# LEDs.net
KiCad netlist of a schematic drawn in Altium Designer
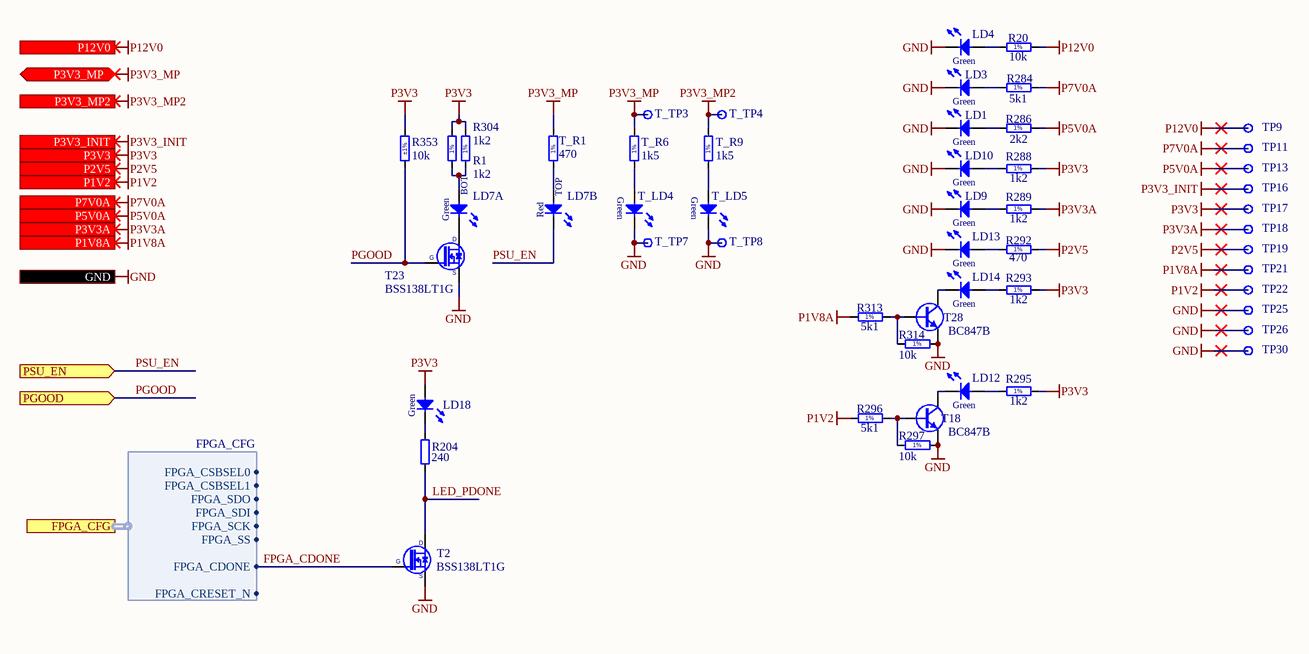
[diagram p0: LEDs.SchDoc]

(export (version "E")
  (design (tool "Eeschema 10.0.6"))
  (components
    (comp (ref "LD1")
      (value "Green")
      (footprint "LED_KINGBRIGHT_KPH-1608CGCK")
      (description "LED Green 1C 2A")
      (fields
        (field (name "PART NUMBER") "LED_KINGBRIGHT_KPH-1608CGCK")
        (field (name "MANUFACTURER") "KINGBRIGHT")
        (field (name "AUTHOR") "CERN DEM JLC")
      )
      (libsource (lib "ICs And Semiconductors") (part "LED Green 1C 2A"))
    )
    (comp (ref "LD3")
      (value "Green")
      (footprint "LED_KINGBRIGHT_KPH-1608CGCK")
      (description "LED Green 1C 2A")
      (fields
        (field (name "PART NUMBER") "LED_KINGBRIGHT_KPH-1608CGCK")
        (field (name "MANUFACTURER") "KINGBRIGHT")
        (field (name "AUTHOR") "CERN DEM JLC")
      )
      (libsource (lib "ICs And Semiconductors") (part "LED Green 1C 2A"))
    )
    (comp (ref "LD4")
      (value "Green")
      (footprint "LED_KINGBRIGHT_KPH-1608CGCK")
      (description "LED Green 1C 2A")
      (fields
        (field (name "PART NUMBER") "LED_KINGBRIGHT_KPH-1608CGCK")
        (field (name "MANUFACTURER") "KINGBRIGHT")
        (field (name "AUTHOR") "CERN DEM JLC")
      )
      (libsource (lib "ICs And Semiconductors") (part "LED Green 1C 2A"))
    )
    (comp (ref "LD7")
      (value "Red/Green")
      (footprint "LED_DIALIGHT_571-0112F")
      (description "2x LED  Botom Green, Top Red")
      (fields
        (field (name "PART NUMBER") "LED_DIALIGHT_571-0112F")
        (field (name "MANUFACTURER") "DIALIGHT")
        (field (name "AUTHOR") "CERN DEM JLC")
      )
      (libsource (lib "ICs And Semiconductors") (part "LED x2 G-1C2A-BOT_R-3C4A-TOP"))
    )
    (comp (ref "LD9")
      (value "Green")
      (footprint "LED_KINGBRIGHT_KPH-1608CGCK")
      (description "LED Green 1C 2A")
      (fields
        (field (name "PART NUMBER") "LED_KINGBRIGHT_KPH-1608CGCK")
        (field (name "MANUFACTURER") "KINGBRIGHT")
        (field (name "AUTHOR") "CERN DEM JLC")
      )
      (libsource (lib "ICs And Semiconductors") (part "LED Green 1C 2A"))
    )
    (comp (ref "LD10")
      (value "Green")
      (footprint "LED_KINGBRIGHT_KPH-1608CGCK")
      (description "LED Green 1C 2A")
      (fields
        (field (name "PART NUMBER") "LED_KINGBRIGHT_KPH-1608CGCK")
        (field (name "MANUFACTURER") "KINGBRIGHT")
        (field (name "AUTHOR") "CERN DEM JLC")
      )
      (libsource (lib "ICs And Semiconductors") (part "LED Green 1C 2A"))
    )
    (comp (ref "LD12")
      (value "Green")
      (footprint "LED_KINGBRIGHT_KPH-1608CGCK")
      (description "LED Green 1C 2A")
      (fields
        (field (name "PART NUMBER") "LED_KINGBRIGHT_KPH-1608CGCK")
        (field (name "MANUFACTURER") "KINGBRIGHT")
        (field (name "AUTHOR") "CERN DEM JLC")
      )
      (libsource (lib "ICs And Semiconductors") (part "LED Green 1C 2A"))
    )
    (comp (ref "LD13")
      (value "Green")
      (footprint "LED_KINGBRIGHT_KPH-1608CGCK")
      (description "LED Green 1C 2A")
      (fields
        (field (name "PART NUMBER") "LED_KINGBRIGHT_KPH-1608CGCK")
        (field (name "MANUFACTURER") "KINGBRIGHT")
        (field (name "AUTHOR") "CERN DEM JLC")
      )
      (libsource (lib "ICs And Semiconductors") (part "LED Green 1C 2A"))
    )
    (comp (ref "LD14")
      (value "Green")
      (footprint "LED_KINGBRIGHT_KPH-1608CGCK")
      (description "LED Green 1C 2A")
      (fields
        (field (name "PART NUMBER") "LED_KINGBRIGHT_KPH-1608CGCK")
        (field (name "MANUFACTURER") "KINGBRIGHT")
        (field (name "AUTHOR") "CERN DEM JLC")
      )
      (libsource (lib "ICs And Semiconductors") (part "LED Green 1C 2A"))
    )
    (comp (ref "LD18")
      (value "Green")
      (footprint "LED_AVAGO_HSME-C120")
      (description "LED Green 1C 2A")
      (fields
        (field (name "PART NUMBER") "LED_AVAGO_HSME-C120")
        (field (name "MANUFACTURER") "AVAGO TECHNOLOGIES")
        (field (name "AUTHOR") "CERN DEM JMW")
      )
      (libsource (lib "ICs And Semiconductors") (part "LED Green 1C 2A"))
    )
    (comp (ref "R1")
      (value "1k2")
      (footprint "RESC1608X55N")
      (description "Resistor - 1%")
      (fields
        (field (name "PART NUMBER") "R0603_1K2_1%_0.1W_100PPM")
        (field (name "POWER") "0.1W")
        (field (name "AUTHOR") "CERN DEM JLC")
      )
      (libsource (lib "Resistors") (part "Resistor - 1%"))
    )
    (comp (ref "R20")
      (value "10k")
      (footprint "RESC1005X40N")
      (description "Resistor - 1%")
      (fields
        (field (name "PART NUMBER") "R0402_10K_1%_0.0625W_100PPM")
        (field (name "POWER") "0.0625W")
        (field (name "AUTHOR") "CERN DEM JLC")
      )
      (libsource (lib "Resistors") (part "Resistor - 1%"))
    )
    (comp (ref "R204")
      (value "240")
      (footprint "RESC1005X40N")
      (description "Resistor - 1%")
      (fields
        (field (name "PART NUMBER") "R0402_240R_1%_0.0625W_100PPM")
        (field (name "POWER") "0.0625W")
        (field (name "AUTHOR") "CERN DEM JLC")
      )
      (libsource (lib "Resistors") (part "Resistor - 1%"))
    )
    (comp (ref "R284")
      (value "5k1")
      (footprint "RESC1005X40N")
      (description "Resistor - 1%")
      (fields
        (field (name "PART NUMBER") "R0402_5K1_1%_0.0625W_100PPM")
        (field (name "POWER") "0.0625W")
        (field (name "AUTHOR") "CERN DEM JLC")
      )
      (libsource (lib "Resistors") (part "Resistor - 1%"))
    )
    (comp (ref "R286")
      (value "2k2")
      (footprint "RESC1005X40N")
      (description "Resistor - 1%")
      (fields
        (field (name "PART NUMBER") "R0402_2K2_1%_0.0625W_100PPM")
        (field (name "POWER") "0.0625W")
        (field (name "AUTHOR") "CERN DEM JLC")
      )
      (libsource (lib "Resistors") (part "Resistor - 1%"))
    )
    (comp (ref "R288")
      (value "1k2")
      (footprint "RESC1608X55N")
      (description "Resistor - 1%")
      (fields
        (field (name "PART NUMBER") "R0603_1K2_1%_0.1W_100PPM")
        (field (name "POWER") "0.1W")
        (field (name "AUTHOR") "CERN DEM JLC")
      )
      (libsource (lib "Resistors") (part "Resistor - 1%"))
    )
    (comp (ref "R289")
      (value "1k2")
      (footprint "RESC1608X55N")
      (description "Resistor - 1%")
      (fields
        (field (name "PART NUMBER") "R0603_1K2_1%_0.1W_100PPM")
        (field (name "POWER") "0.1W")
        (field (name "AUTHOR") "CERN DEM JLC")
      )
      (libsource (lib "Resistors") (part "Resistor - 1%"))
    )
    (comp (ref "R292")
      (value "470")
      (footprint "RESC1005X40N")
      (description "Resistor - 1%")
      (fields
        (field (name "PART NUMBER") "R0402_470R_1%_0.0625W_100PPM")
        (field (name "POWER") "0.0625W")
        (field (name "AUTHOR") "CERN DEM JLC")
      )
      (libsource (lib "Resistors") (part "Resistor - 1%"))
    )
    (comp (ref "R293")
      (value "1k2")
      (footprint "RESC1608X55N")
      (description "Resistor - 1%")
      (fields
        (field (name "PART NUMBER") "R0603_1K2_1%_0.1W_100PPM")
        (field (name "POWER") "0.1W")
        (field (name "AUTHOR") "CERN DEM JLC")
      )
      (libsource (lib "Resistors") (part "Resistor - 1%"))
    )
    (comp (ref "R295")
      (value "1k2")
      (footprint "RESC1608X55N")
      (description "Resistor - 1%")
      (fields
        (field (name "PART NUMBER") "R0603_1K2_1%_0.1W_100PPM")
        (field (name "POWER") "0.1W")
        (field (name "AUTHOR") "CERN DEM JLC")
      )
      (libsource (lib "Resistors") (part "Resistor - 1%"))
    )
    (comp (ref "R296")
      (value "5k1")
      (footprint "RESC1005X40N")
      (description "Resistor - 1%")
      (fields
        (field (name "PART NUMBER") "R0402_5K1_1%_0.0625W_100PPM")
        (field (name "POWER") "0.0625W")
        (field (name "AUTHOR") "CERN DEM JLC")
      )
      (libsource (lib "Resistors") (part "Resistor - 1%"))
    )
    (comp (ref "R297")
      (value "10k")
      (footprint "RESC1005X40N")
      (description "Resistor - 1%")
      (fields
        (field (name "PART NUMBER") "R0402_10K_1%_0.0625W_100PPM")
        (field (name "POWER") "0.0625W")
        (field (name "AUTHOR") "CERN DEM JLC")
      )
      (libsource (lib "Resistors") (part "Resistor - 1%"))
    )
    (comp (ref "R304")
      (value "1k2")
      (footprint "RESC1608X55N")
      (description "Resistor - 1%")
      (fields
        (field (name "PART NUMBER") "R0603_1K2_1%_0.1W_100PPM")
        (field (name "POWER") "0.1W")
        (field (name "AUTHOR") "CERN DEM JLC")
      )
      (libsource (lib "Resistors") (part "Resistor - 1%"))
    )
    (comp (ref "R313")
      (value "5k1")
      (footprint "RESC1005X40N")
      (description "Resistor - 1%")
      (fields
        (field (name "PART NUMBER") "R0402_5K1_1%_0.0625W_100PPM")
        (field (name "POWER") "0.0625W")
        (field (name "AUTHOR") "CERN DEM JLC")
      )
      (libsource (lib "Resistors") (part "Resistor - 1%"))
    )
    (comp (ref "R314")
      (value "10k")
      (footprint "RESC1005X40N")
      (description "Resistor - 1%")
      (fields
        (field (name "PART NUMBER") "R0402_10K_1%_0.0625W_100PPM")
        (field (name "POWER") "0.0625W")
        (field (name "AUTHOR") "CERN DEM JLC")
      )
      (libsource (lib "Resistors") (part "Resistor - 1%"))
    )
    (comp (ref "R353")
      (value "10k")
      (footprint "RESC1005X40N")
      (description "Resistor - 1%")
      (fields
        (field (name "TOLERANCE") "±1%")
        (field (name "PART NUMBER") "R0402_10K_1%_0.0625W_100PPM")
        (field (name "POWER") "0.0625W")
        (field (name "AUTHOR") "CERN DEM JLC")
      )
      (libsource (lib "Resistors") (part "Resistor - 1%"))
    )
    (comp (ref "T2")
      (value "BSS138LT1G")
      (footprint "SOT95P240X110-3N")
      (description "N-CHANNEL MOSFET WITH DIODE")
      (fields (field (name "MANUFACTURER") "ON SEMICONDUCTOR") (field (name "AUTHOR") "CERN DEM JLC"))
      (libsource (lib "ICs And Semiconductors") (part "N-MOSFET-D 1G 2S 3D"))
    )
    (comp (ref "T18")
      (value "BC847B")
      (footprint "SOT95P230X110-3N")
      (description "NPN Transistor")
      (fields (field (name "MANUFACTURER") "NXP SEMICONDUCTORS") (field (name "AUTHOR") "CERN DEM JLC"))
      (libsource (lib "ICs And Semiconductors") (part "NPN B1 E2 C3"))
    )
    (comp (ref "T23")
      (value "BSS138LT1G")
      (footprint "SOT95P240X110-3N")
      (description "N-CHANNEL MOSFET WITH DIODE")
      (fields
        (field (name "MANUFACTURER") "ON SEMICONDUCTOR")
        (field (name "MANUFACTURER PART NUMBER") "BSS138L")
        (field (name "AUTHOR") "CERN DEM JLC")
      )
      (libsource (lib "ICs And Semiconductors") (part "N-MOSFET-D 1G 2S 3D"))
    )
    (comp (ref "T28")
      (value "BC847B")
      (footprint "SOT95P230X110-3N")
      (description "NPN Transistor")
      (fields (field (name "MANUFACTURER") "NXP SEMICONDUCTORS") (field (name "AUTHOR") "CERN DEM JLC"))
      (libsource (lib "ICs And Semiconductors") (part "NPN B1 E2 C3"))
    )
    (comp (ref "TP9")
      (value "Test Point")
      (footprint "TPS127")
      (fields (field (name "PART NUMBER") "SMD_PAD_1.27X1.27MM") (field (name "AUTHOR") "CERN DEM JLC"))
      (libsource (lib "Eletro-mechanical") (part "Test Point"))
    )
    (comp (ref "TP11")
      (value "Test Point")
      (footprint "TPS127")
      (fields (field (name "PART NUMBER") "SMD_PAD_1.27X1.27MM") (field (name "AUTHOR") "CERN DEM JLC"))
      (libsource (lib "Eletro-mechanical") (part "Test Point"))
    )
    (comp (ref "TP13")
      (value "Test Point")
      (footprint "TPS127")
      (fields (field (name "PART NUMBER") "SMD_PAD_1.27X1.27MM") (field (name "AUTHOR") "CERN DEM JLC"))
      (libsource (lib "Eletro-mechanical") (part "Test Point"))
    )
    (comp (ref "TP16")
      (value "Test Point")
      (footprint "TPS127")
      (fields (field (name "PART NUMBER") "SMD_PAD_1.27X1.27MM") (field (name "AUTHOR") "CERN DEM JLC"))
      (libsource (lib "Eletro-mechanical") (part "Test Point"))
    )
    (comp (ref "TP17")
      (value "Test Point")
      (footprint "TPS127")
      (fields (field (name "PART NUMBER") "SMD_PAD_1.27X1.27MM") (field (name "AUTHOR") "CERN DEM JLC"))
      (libsource (lib "Eletro-mechanical") (part "Test Point"))
    )
    (comp (ref "TP18")
      (value "Test Point")
      (footprint "TPS127")
      (fields (field (name "PART NUMBER") "SMD_PAD_1.27X1.27MM") (field (name "AUTHOR") "CERN DEM JLC"))
      (libsource (lib "Eletro-mechanical") (part "Test Point"))
    )
    (comp (ref "TP19")
      (value "Test Point")
      (footprint "TPS127")
      (fields (field (name "PART NUMBER") "SMD_PAD_1.27X1.27MM") (field (name "AUTHOR") "CERN DEM JLC"))
      (libsource (lib "Eletro-mechanical") (part "Test Point"))
    )
    (comp (ref "TP21")
      (value "Test Point")
      (footprint "TPS127")
      (fields (field (name "PART NUMBER") "SMD_PAD_1.27X1.27MM") (field (name "AUTHOR") "CERN DEM JLC"))
      (libsource (lib "Eletro-mechanical") (part "Test Point"))
    )
    (comp (ref "TP22")
      (value "Test Point")
      (footprint "TPS127")
      (fields (field (name "PART NUMBER") "SMD_PAD_1.27X1.27MM") (field (name "AUTHOR") "CERN DEM JLC"))
      (libsource (lib "Eletro-mechanical") (part "Test Point"))
    )
    (comp (ref "TP25")
      (value "Test Point")
      (footprint "TPS127")
      (fields (field (name "PART NUMBER") "SMD_PAD_1.27X1.27MM") (field (name "AUTHOR") "CERN DEM JLC"))
      (libsource (lib "Eletro-mechanical") (part "Test Point"))
    )
    (comp (ref "TP26")
      (value "Test Point")
      (footprint "TPS127")
      (fields (field (name "PART NUMBER") "SMD_PAD_1.27X1.27MM") (field (name "AUTHOR") "CERN DEM JLC"))
      (libsource (lib "Eletro-mechanical") (part "Test Point"))
    )
    (comp (ref "TP30")
      (value "Test Point")
      (footprint "TPS127")
      (fields (field (name "PART NUMBER") "SMD_PAD_1.27X1.27MM") (field (name "AUTHOR") "CERN DEM JLC"))
      (libsource (lib "Eletro-mechanical") (part "Test Point"))
    )
    (comp (ref "T_LD4")
      (value "Green")
      (footprint "LED_KINGBRIGHT_KPH-1608CGCK")
      (description "LED Green 1C 2A")
      (fields
        (field (name "PART NUMBER") "LED_KINGBRIGHT_KPH-1608CGCK")
        (field (name "MANUFACTURER") "KINGBRIGHT")
        (field (name "AUTHOR") "CERN DEM JLC")
      )
      (libsource (lib "") (part "LED Green 1C 2A_1"))
    )
    (comp (ref "T_LD5")
      (value "Green")
      (footprint "LED_KINGBRIGHT_KPH-1608CGCK")
      (description "LED Green 1C 2A")
      (fields
        (field (name "PART NUMBER") "LED_KINGBRIGHT_KPH-1608CGCK")
        (field (name "MANUFACTURER") "KINGBRIGHT")
        (field (name "AUTHOR") "CERN DEM JLC")
      )
      (libsource (lib "") (part "LED Green 1C 2A_1"))
    )
    (comp (ref "T_R1")
      (value "470")
      (footprint "RESC1005X40N")
      (description "Resistor - 1%")
      (fields
        (field (name "PART NUMBER") "R0402_470R_1%_0.0625W_100PPM")
        (field (name "POWER") "0.0625W")
        (field (name "AUTHOR") "CERN DEM JLC")
      )
      (libsource (lib "Resistors") (part "Resistor - 1%"))
    )
    (comp (ref "T_R6")
      (value "1k5")
      (footprint "RESC1608X55N")
      (description "Resistor - 1%")
      (fields
        (field (name "PART NUMBER") "R0603_1K5_1%_0.1W_100PPM")
        (field (name "POWER") "0.1W")
        (field (name "AUTHOR") "CERN DEM JLC")
      )
      (libsource (lib "Resistors") (part "Resistor - 1%"))
    )
    (comp (ref "T_R9")
      (value "1k5")
      (footprint "RESC1608X55N")
      (description "Resistor - 1%")
      (fields
        (field (name "PART NUMBER") "R0603_1K5_1%_0.1W_100PPM")
        (field (name "POWER") "0.1W")
        (field (name "AUTHOR") "CERN DEM JLC")
      )
      (libsource (lib "Resistors") (part "Resistor - 1%"))
    )
    (comp (ref "T_TP3")
      (value "Test Point")
      (footprint "TPS127")
      (fields (field (name "PART NUMBER") "SMD_PAD_1.27X1.27MM") (field (name "AUTHOR") "CERN DEM JLC"))
      (libsource (lib "Eletro-mechanical") (part "Test Point"))
    )
    (comp (ref "T_TP4")
      (value "Test Point")
      (footprint "TPS127")
      (fields (field (name "PART NUMBER") "SMD_PAD_1.27X1.27MM") (field (name "AUTHOR") "CERN DEM JLC"))
      (libsource (lib "Eletro-mechanical") (part "Test Point"))
    )
    (comp (ref "T_TP7")
      (value "Test Point")
      (footprint "TPS127")
      (fields (field (name "PART NUMBER") "SMD_PAD_1.27X1.27MM") (field (name "AUTHOR") "CERN DEM JLC"))
      (libsource (lib "Eletro-mechanical") (part "Test Point"))
    )
    (comp (ref "T_TP8")
      (value "Test Point")
      (footprint "TPS127")
      (fields (field (name "PART NUMBER") "SMD_PAD_1.27X1.27MM") (field (name "AUTHOR") "CERN DEM JLC"))
      (libsource (lib "Eletro-mechanical") (part "Test Point"))
    )
  )
  (nets
    (net (code "2") (name "/FPGA_CDONE") (class "Default")
      (node (ref "T2") (pin "1") (pinfunction "G_1") (pintype "passive"))
    )
    (net (code "3") (name "/LED_PDONE") (class "Default")
      (node (ref "R204") (pin "1") (pinfunction "1_1") (pintype "passive"))
      (node (ref "T2") (pin "3") (pinfunction "D_3") (pintype "passive"))
    )
    (net (code "4") (name "/PGOOD") (class "Default")
      (node (ref "R353") (pin "1") (pinfunction "1_1") (pintype "passive"))
      (node (ref "T23") (pin "1") (pinfunction "G_1") (pintype "passive"))
    )
    (net (code "5") (name "/PSU_EN") (class "Default")
      (node (ref "LD7") (pin "3") (pinfunction "C_3") (pintype "passive"))
    )
    (net (code "7") (name "GND") (class "Default")
      (node (ref "LD1") (pin "1") (pinfunction "C_1") (pintype "passive"))
      (node (ref "LD10") (pin "1") (pinfunction "C_1") (pintype "passive"))
      (node (ref "LD13") (pin "1") (pinfunction "C_1") (pintype "passive"))
      (node (ref "LD3") (pin "1") (pinfunction "C_1") (pintype "passive"))
      (node (ref "LD4") (pin "1") (pinfunction "C_1") (pintype "passive"))
      (node (ref "LD9") (pin "1") (pinfunction "C_1") (pintype "passive"))
      (node (ref "R297") (pin "2") (pinfunction "2_2") (pintype "passive"))
      (node (ref "R314") (pin "2") (pinfunction "2_2") (pintype "passive"))
      (node (ref "T18") (pin "2") (pinfunction "E_2") (pintype "passive"))
      (node (ref "T2") (pin "2") (pinfunction "S_2") (pintype "passive"))
      (node (ref "T23") (pin "2") (pinfunction "S_2") (pintype "passive"))
      (node (ref "T28") (pin "2") (pinfunction "E_2") (pintype "passive"))
      (node (ref "TP25") (pin "1") (pinfunction "1_1") (pintype "bidirectional"))
      (node (ref "TP26") (pin "1") (pinfunction "1_1") (pintype "bidirectional"))
      (node (ref "TP30") (pin "1") (pinfunction "1_1") (pintype "bidirectional"))
      (node (ref "T_LD4") (pin "1") (pinfunction "C_1") (pintype "passive"))
      (node (ref "T_LD5") (pin "1") (pinfunction "C_1") (pintype "passive"))
      (node (ref "T_TP7") (pin "1") (pinfunction "1_1") (pintype "bidirectional"))
      (node (ref "T_TP8") (pin "1") (pinfunction "1_1") (pintype "bidirectional"))
    )
    (net (code "8") (name "Net-(LD1-A)") (class "Default")
      (node (ref "LD1") (pin "2") (pinfunction "A_2") (pintype "passive"))
      (node (ref "R286") (pin "1") (pinfunction "1_1") (pintype "passive"))
    )
    (net (code "9") (name "Net-(LD3-A)") (class "Default")
      (node (ref "LD3") (pin "2") (pinfunction "A_2") (pintype "passive"))
      (node (ref "R284") (pin "1") (pinfunction "1_1") (pintype "passive"))
    )
    (net (code "10") (name "Net-(LD4-A)") (class "Default")
      (node (ref "LD4") (pin "2") (pinfunction "A_2") (pintype "passive"))
      (node (ref "R20") (pin "1") (pinfunction "1_1") (pintype "passive"))
    )
    (net (code "11") (name "Net-(LD7A-A)") (class "Default")
      (node (ref "LD7") (pin "2") (pinfunction "A_2") (pintype "passive"))
      (node (ref "R1") (pin "1") (pinfunction "1_1") (pintype "passive"))
      (node (ref "R304") (pin "1") (pinfunction "1_1") (pintype "passive"))
    )
    (net (code "12") (name "Net-(LD7A-C)") (class "Default")
      (node (ref "LD7") (pin "1") (pinfunction "C_1") (pintype "passive"))
      (node (ref "T23") (pin "3") (pinfunction "D_3") (pintype "passive"))
    )
    (net (code "13") (name "Net-(LD7B-A)") (class "Default")
      (node (ref "LD7") (pin "4") (pinfunction "A_4") (pintype "passive"))
      (node (ref "T_R1") (pin "2") (pinfunction "2_2") (pintype "passive"))
    )
    (net (code "14") (name "Net-(LD9-A)") (class "Default")
      (node (ref "LD9") (pin "2") (pinfunction "A_2") (pintype "passive"))
      (node (ref "R289") (pin "1") (pinfunction "1_1") (pintype "passive"))
    )
    (net (code "15") (name "Net-(LD10-A)") (class "Default")
      (node (ref "LD10") (pin "2") (pinfunction "A_2") (pintype "passive"))
      (node (ref "R288") (pin "1") (pinfunction "1_1") (pintype "passive"))
    )
    (net (code "16") (name "Net-(LD12-A)") (class "Default")
      (node (ref "LD12") (pin "2") (pinfunction "A_2") (pintype "passive"))
      (node (ref "R295") (pin "1") (pinfunction "1_1") (pintype "passive"))
    )
    (net (code "17") (name "Net-(LD12-C)") (class "Default")
      (node (ref "LD12") (pin "1") (pinfunction "C_1") (pintype "passive"))
      (node (ref "T18") (pin "3") (pinfunction "C_3") (pintype "passive"))
    )
    (net (code "18") (name "Net-(LD13-A)") (class "Default")
      (node (ref "LD13") (pin "2") (pinfunction "A_2") (pintype "passive"))
      (node (ref "R292") (pin "2") (pinfunction "2_2") (pintype "passive"))
    )
    (net (code "19") (name "Net-(LD14-A)") (class "Default")
      (node (ref "LD14") (pin "2") (pinfunction "A_2") (pintype "passive"))
      (node (ref "R293") (pin "1") (pinfunction "1_1") (pintype "passive"))
    )
    (net (code "20") (name "Net-(LD14-C)") (class "Default")
      (node (ref "LD14") (pin "1") (pinfunction "C_1") (pintype "passive"))
      (node (ref "T28") (pin "3") (pinfunction "C_3") (pintype "passive"))
    )
    (net (code "21") (name "Net-(LD18-C)") (class "Default")
      (node (ref "LD18") (pin "1") (pinfunction "C_1") (pintype "passive"))
      (node (ref "R204") (pin "2") (pinfunction "2_2") (pintype "passive"))
    )
    (net (code "22") (name "Net-(T18-B)") (class "Default")
      (node (ref "R296") (pin "2") (pinfunction "2_2") (pintype "passive"))
      (node (ref "R297") (pin "1") (pinfunction "1_1") (pintype "passive"))
      (node (ref "T18") (pin "1") (pinfunction "B_1") (pintype "passive"))
    )
    (net (code "23") (name "Net-(T28-B)") (class "Default")
      (node (ref "R313") (pin "2") (pinfunction "2_2") (pintype "passive"))
      (node (ref "R314") (pin "1") (pinfunction "1_1") (pintype "passive"))
      (node (ref "T28") (pin "1") (pinfunction "B_1") (pintype "passive"))
    )
    (net (code "24") (name "Net-(T_LD4-A)") (class "Default")
      (node (ref "T_LD4") (pin "2") (pinfunction "A_2") (pintype "passive"))
      (node (ref "T_R6") (pin "1") (pinfunction "1_1") (pintype "passive"))
    )
    (net (code "25") (name "Net-(T_LD5-A)") (class "Default")
      (node (ref "T_LD5") (pin "2") (pinfunction "A_2") (pintype "passive"))
      (node (ref "T_R9") (pin "1") (pinfunction "1_1") (pintype "passive"))
    )
    (net (code "26") (name "P1V2") (class "Default")
      (node (ref "R296") (pin "1") (pinfunction "1_1") (pintype "passive"))
      (node (ref "TP22") (pin "1") (pinfunction "1_1") (pintype "bidirectional"))
    )
    (net (code "27") (name "P1V8A") (class "Default")
      (node (ref "R313") (pin "1") (pinfunction "1_1") (pintype "passive"))
      (node (ref "TP21") (pin "1") (pinfunction "1_1") (pintype "bidirectional"))
    )
    (net (code "28") (name "P2V5") (class "Default")
      (node (ref "R292") (pin "1") (pinfunction "1_1") (pintype "passive"))
      (node (ref "TP19") (pin "1") (pinfunction "1_1") (pintype "bidirectional"))
    )
    (net (code "29") (name "P3V3") (class "Default")
      (node (ref "LD18") (pin "2") (pinfunction "A_2") (pintype "passive"))
      (node (ref "R1") (pin "2") (pinfunction "2_2") (pintype "passive"))
      (node (ref "R288") (pin "2") (pinfunction "2_2") (pintype "passive"))
      (node (ref "R293") (pin "2") (pinfunction "2_2") (pintype "passive"))
      (node (ref "R295") (pin "2") (pinfunction "2_2") (pintype "passive"))
      (node (ref "R304") (pin "2") (pinfunction "2_2") (pintype "passive"))
      (node (ref "R353") (pin "2") (pinfunction "2_2") (pintype "passive"))
      (node (ref "TP17") (pin "1") (pinfunction "1_1") (pintype "bidirectional"))
    )
    (net (code "30") (name "P3V3A") (class "Default")
      (node (ref "R289") (pin "2") (pinfunction "2_2") (pintype "passive"))
      (node (ref "TP18") (pin "1") (pinfunction "1_1") (pintype "bidirectional"))
    )
    (net (code "31") (name "P3V3_INIT") (class "Default")
      (node (ref "TP16") (pin "1") (pinfunction "1_1") (pintype "bidirectional"))
    )
    (net (code "32") (name "P3V3_MP") (class "Default")
      (node (ref "T_R1") (pin "1") (pinfunction "1_1") (pintype "passive"))
      (node (ref "T_R6") (pin "2") (pinfunction "2_2") (pintype "passive"))
      (node (ref "T_TP3") (pin "1") (pinfunction "1_1") (pintype "bidirectional"))
    )
    (net (code "33") (name "P3V3_MP2") (class "Default")
      (node (ref "T_R9") (pin "2") (pinfunction "2_2") (pintype "passive"))
      (node (ref "T_TP4") (pin "1") (pinfunction "1_1") (pintype "bidirectional"))
    )
    (net (code "34") (name "P5V0A") (class "Default")
      (node (ref "R286") (pin "2") (pinfunction "2_2") (pintype "passive"))
      (node (ref "TP13") (pin "1") (pinfunction "1_1") (pintype "bidirectional"))
    )
    (net (code "35") (name "P7V0A") (class "Default")
      (node (ref "R284") (pin "2") (pinfunction "2_2") (pintype "passive"))
      (node (ref "TP11") (pin "1") (pinfunction "1_1") (pintype "bidirectional"))
    )
    (net (code "36") (name "P12V0") (class "Default")
      (node (ref "R20") (pin "2") (pinfunction "2_2") (pintype "passive"))
      (node (ref "TP9") (pin "1") (pinfunction "1_1") (pintype "bidirectional"))
    )
  )
)
